# Control.net
KiCad netlist of a schematic drawn in Altium Designer
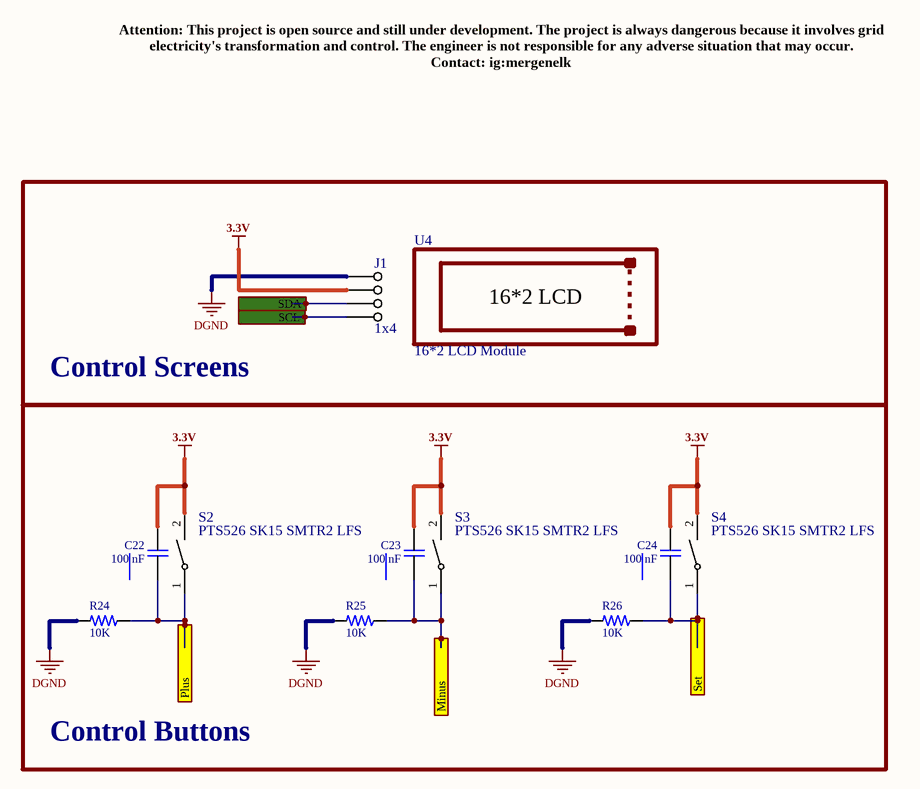
[diagram p0: Control.SchDoc]

(export (version "E")
  (design (tool "Eeschema 10.0.6"))
  (components
    (comp (ref "C22")
      (value "100 nF")
      (footprint "MergenElektronik_Capacitors_Ceramics_SMDs_0603_S_NS")
      (description "Mergen Elektronik - Capacitors - Ceramics - SMDs - 0603 - 100 nF - 16V")
      (fields (field (name "MANUFACTURER") "Samsung Electro-Mechanics") (field (name "TOLERANCE") "±10%"))
      (libsource (lib "MergenElektronik_Capacitors_Ceramics_SMDs") (part "MergenElektronik_Capacitors_Ceramic_SMDs_100nF_16V"))
    )
    (comp (ref "C23")
      (value "100 nF")
      (footprint "MergenElektronik_Capacitors_Ceramics_SMDs_0603_S_NS")
      (description "Mergen Elektronik - Capacitors - Ceramics - SMDs - 0603 - 100 nF - 16V")
      (fields (field (name "MANUFACTURER") "Samsung Electro-Mechanics") (field (name "TOLERANCE") "±10%"))
      (libsource (lib "MergenElektronik_Capacitors_Ceramics_SMDs") (part "MergenElektronik_Capacitors_Ceramic_SMDs_100nF_16V"))
    )
    (comp (ref "C24")
      (value "100 nF")
      (footprint "MergenElektronik_Capacitors_Ceramics_SMDs_0603_S_NS")
      (description "Mergen Elektronik - Capacitors - Ceramics - SMDs - 0603 - 100 nF - 16V")
      (fields (field (name "MANUFACTURER") "Samsung Electro-Mechanics") (field (name "TOLERANCE") "±10%"))
      (libsource (lib "MergenElektronik_Capacitors_Ceramics_SMDs") (part "MergenElektronik_Capacitors_Ceramic_SMDs_100nF_16V"))
    )
    (comp (ref "J1")
      (value "1x4")
      (footprint "MergenElektronik_Connectors_Headers_1x4_Male")
      (description "Mergen Elektronik - Connectors - Headers - 1x4 Male")
      (libsource (lib "MergenElektronik_Connectors_Headers") (part "MergenElektronik_Connectors_Headers_1x4_Male"))
    )
    (comp (ref "R24")
      (value "10K")
      (footprint "MergenElektronik_Resistors_ChipResistors_0603_S_NS")
      (description "Mergen Elektronik - Resistors - Chip Resistors - 0603 - 10K")
      (fields (field (name "MANUFACTURER") "Stackpole Electronics Inc") (field (name "POWER") "1/10W"))
      (libsource (lib "MergenElektronik_Resistors_ChipResistors") (part "MergenElektronik_Resistors_ChipResistors_0603_10K"))
    )
    (comp (ref "R25")
      (value "10K")
      (footprint "MergenElektronik_Resistors_ChipResistors_0603_S_NS")
      (description "Mergen Elektronik - Resistors - Chip Resistors - 0603 - 10K")
      (fields (field (name "MANUFACTURER") "Stackpole Electronics Inc") (field (name "POWER") "1/10W"))
      (libsource (lib "MergenElektronik_Resistors_ChipResistors") (part "MergenElektronik_Resistors_ChipResistors_0603_10K"))
    )
    (comp (ref "R26")
      (value "10K")
      (footprint "MergenElektronik_Resistors_ChipResistors_0603_S_NS")
      (description "Mergen Elektronik - Resistors - Chip Resistors - 0603 - 10K")
      (fields (field (name "MANUFACTURER") "Stackpole Electronics Inc") (field (name "POWER") "1/10W"))
      (libsource (lib "MergenElektronik_Resistors_ChipResistors") (part "MergenElektronik_Resistors_ChipResistors_0603_10K"))
    )
    (comp (ref "S2")
      (value "PTS526 SK15 SMTR2 LFS")
      (footprint "MergenElektronik_Switches_TactileSwitches_PTS526")
      (description "Mergen Elektronik - Switches - Tactile  Switches - PTS526 SK15 SMTR2 LFS")
      (fields (field (name "MANUFACTURER") "C&K"))
      (libsource (lib "MergenElektronik_Switches_TactileSwitches") (part "MergenElektronik_Switches_TactileSwitches_PTS526 SK15 SMTR2 LFS"))
    )
    (comp (ref "S3")
      (value "PTS526 SK15 SMTR2 LFS")
      (footprint "MergenElektronik_Switches_TactileSwitches_PTS526")
      (description "Mergen Elektronik - Switches - Tactile  Switches - PTS526 SK15 SMTR2 LFS")
      (fields (field (name "MANUFACTURER") "C&K"))
      (libsource (lib "MergenElektronik_Switches_TactileSwitches") (part "MergenElektronik_Switches_TactileSwitches_PTS526 SK15 SMTR2 LFS"))
    )
    (comp (ref "S4")
      (value "PTS526 SK15 SMTR2 LFS")
      (footprint "MergenElektronik_Switches_TactileSwitches_PTS526")
      (description "Mergen Elektronik - Switches - Tactile  Switches - PTS526 SK15 SMTR2 LFS")
      (fields (field (name "MANUFACTURER") "C&K"))
      (libsource (lib "MergenElektronik_Switches_TactileSwitches") (part "MergenElektronik_Switches_TactileSwitches_PTS526 SK15 SMTR2 LFS"))
    )
    (comp (ref "U4")
      (value "16*2 LCD Module")
      (footprint "MergenElektronik_Screens_LCDs_16x2Module")
      (description "Mergen Elektronik - Screens - LCDs - 16x2 Module")
      (libsource (lib "MergenElektronik_Screens_LCDs") (part "MergenElektronik_Screens_LCDs_16x2Module"))
    )
  )
  (nets
    (net (code "1") (name "/Minus") (class "Default")
      (node (ref "C23") (pin "2") (pinfunction "2_2") (pintype "passive"))
      (node (ref "R25") (pin "1") (pinfunction "1_1") (pintype "passive"))
      (node (ref "S3") (pin "1") (pinfunction "1_1") (pintype "passive"))
    )
    (net (code "2") (name "/Plus") (class "Default")
      (node (ref "C22") (pin "2") (pinfunction "2_2") (pintype "passive"))
      (node (ref "R24") (pin "1") (pinfunction "1_1") (pintype "passive"))
      (node (ref "S2") (pin "1") (pinfunction "1_1") (pintype "passive"))
    )
    (net (code "3") (name "/SCL") (class "Default")
      (node (ref "J1") (pin "1") (pinfunction "1_1") (pintype "passive"))
    )
    (net (code "4") (name "/SDA") (class "Default")
      (node (ref "J1") (pin "2") (pinfunction "2_2") (pintype "passive"))
    )
    (net (code "5") (name "/Set") (class "Default")
      (node (ref "C24") (pin "2") (pinfunction "2_2") (pintype "passive"))
      (node (ref "R26") (pin "1") (pinfunction "1_1") (pintype "passive"))
      (node (ref "S4") (pin "1") (pinfunction "1_1") (pintype "passive"))
    )
    (net (code "6") (name "3.3V") (class "Default")
      (node (ref "C22") (pin "1") (pinfunction "1_1") (pintype "passive"))
      (node (ref "C23") (pin "1") (pinfunction "1_1") (pintype "passive"))
      (node (ref "C24") (pin "1") (pinfunction "1_1") (pintype "passive"))
      (node (ref "J1") (pin "3") (pinfunction "3_3") (pintype "passive"))
      (node (ref "S2") (pin "2") (pinfunction "2_2") (pintype "passive"))
      (node (ref "S3") (pin "2") (pinfunction "2_2") (pintype "passive"))
      (node (ref "S4") (pin "2") (pinfunction "2_2") (pintype "passive"))
    )
    (net (code "7") (name "DGND") (class "Default")
      (node (ref "J1") (pin "4") (pinfunction "4_4") (pintype "passive"))
      (node (ref "R24") (pin "2") (pinfunction "2_2") (pintype "passive"))
      (node (ref "R25") (pin "2") (pinfunction "2_2") (pintype "passive"))
      (node (ref "R26") (pin "2") (pinfunction "2_2") (pintype "passive"))
    )
  )
)
